# batteryCharger.net
KiCad netlist of a schematic drawn in EAGLE
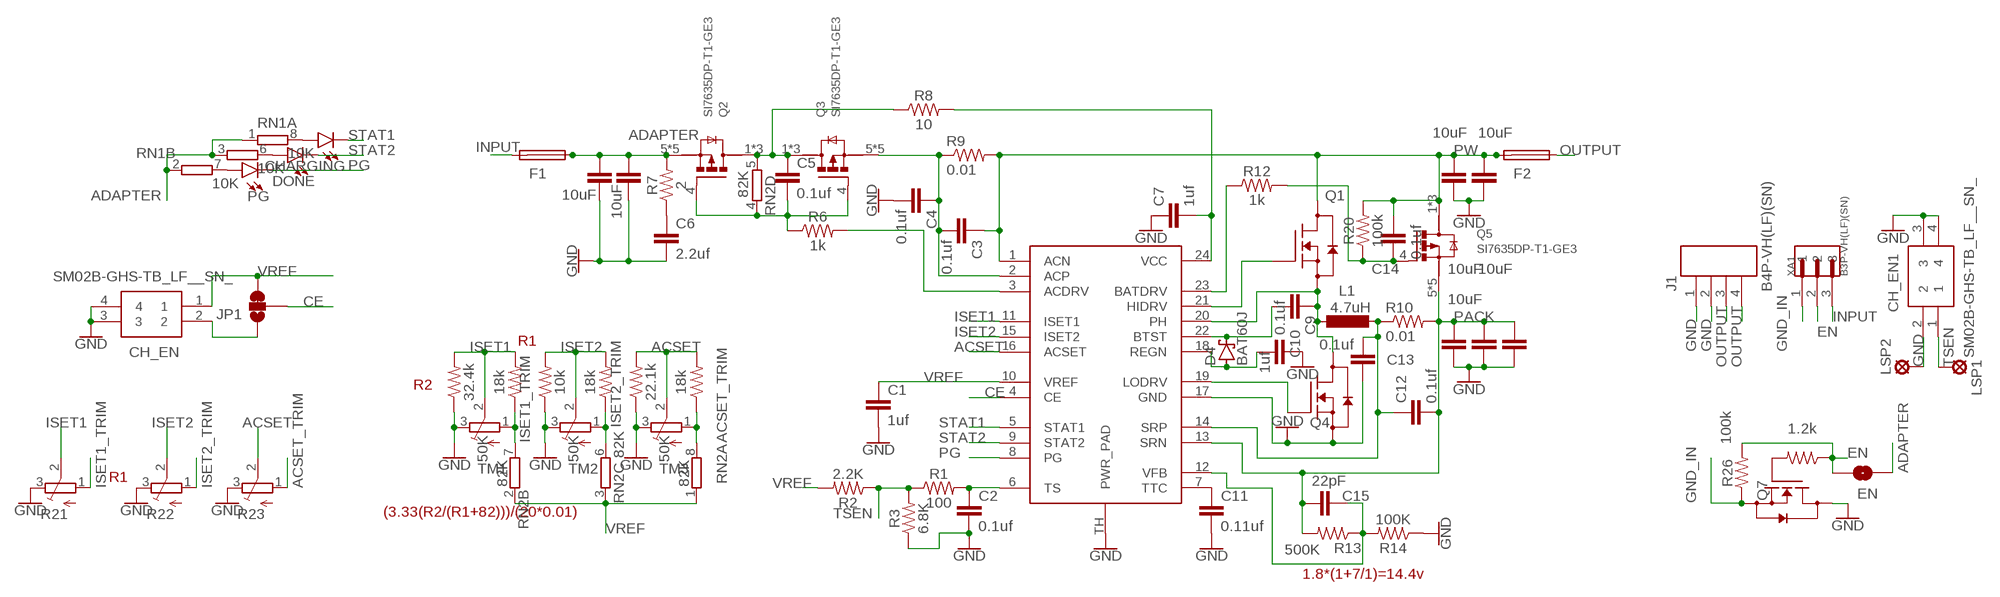
[diagram p0: schematic, sheet 1]

(export (version "E")
  (design (tool "Eeschema 10.0.6"))
  (components
    (comp (ref "C1")
      (value "1uf")
      (footprint "eagle-import:C0603")
      (libsource (lib "eagle-import") (part "C-EUC0603"))
    )
    (comp (ref "C2")
      (value "0.1uf")
      (footprint "eagle-import:C0603")
      (libsource (lib "eagle-import") (part "C-EUC0603"))
    )
    (comp (ref "C3")
      (value "0.1uf")
      (footprint "eagle-import:C0603")
      (libsource (lib "eagle-import") (part "C-EUC0603"))
    )
    (comp (ref "C4")
      (value "0.1uf")
      (footprint "eagle-import:C0603")
      (libsource (lib "eagle-import") (part "C-EUC0603"))
    )
    (comp (ref "C5")
      (value "0.1uf")
      (footprint "eagle-import:C0603")
      (libsource (lib "eagle-import") (part "C-EUC0603"))
    )
    (comp (ref "C6")
      (value "2.2uf")
      (footprint "eagle-import:C0603")
      (libsource (lib "eagle-import") (part "C-EUC0603"))
    )
    (comp (ref "C7")
      (value "1uf")
      (footprint "eagle-import:C0603")
      (libsource (lib "eagle-import") (part "C-EUC0603"))
    )
    (comp (ref "C9")
      (value "0.1uf")
      (footprint "eagle-import:C0603")
      (libsource (lib "eagle-import") (part "C-EUC0603"))
    )
    (comp (ref "C10")
      (value "1uf")
      (footprint "eagle-import:C0603")
      (libsource (lib "eagle-import") (part "C-EUC0603"))
    )
    (comp (ref "C11")
      (value "0.11uf")
      (footprint "eagle-import:C0603")
      (libsource (lib "eagle-import") (part "C-EUC0603"))
    )
    (comp (ref "C12")
      (value "0.1uf")
      (footprint "eagle-import:C0603")
      (libsource (lib "eagle-import") (part "C-EUC0603"))
    )
    (comp (ref "C13")
      (value "0.1uf")
      (footprint "eagle-import:C0603")
      (libsource (lib "eagle-import") (part "C-EUC0603"))
    )
    (comp (ref "C14")
      (value "0.1uf")
      (footprint "eagle-import:C0603")
      (libsource (lib "eagle-import") (part "C-EUC0603"))
    )
    (comp (ref "C15")
      (value "22pF")
      (footprint "eagle-import:C0603")
      (libsource (lib "eagle-import") (part "C-EUC0603"))
    )
    (comp (ref "C16")
      (value "10uF")
      (footprint "eagle-import:C1206")
      (libsource (lib "eagle-import") (part "C-EUC1206"))
    )
    (comp (ref "C17")
      (value "10uF")
      (footprint "eagle-import:C1206")
      (libsource (lib "eagle-import") (part "C-EUC1206"))
    )
    (comp (ref "C18")
      (value "10uF")
      (footprint "eagle-import:C1206")
      (libsource (lib "eagle-import") (part "C-EUC1206"))
    )
    (comp (ref "C19")
      (value "10uF")
      (footprint "eagle-import:C1206")
      (libsource (lib "eagle-import") (part "C-EUC1206"))
    )
    (comp (ref "C20")
      (value "10uF")
      (footprint "eagle-import:C1206")
      (libsource (lib "eagle-import") (part "C-EUC1206"))
    )
    (comp (ref "C21")
      (value "10uF")
      (footprint "eagle-import:C1206")
      (libsource (lib "eagle-import") (part "C-EUC1206"))
    )
    (comp (ref "C22")
      (value "10uF")
      (footprint "eagle-import:C1206")
      (libsource (lib "eagle-import") (part "C-EUC1206"))
    )
    (comp (ref "CHARGING")
      (value "LED1206")
      (footprint "eagle-import:LED-1206")
      (libsource (lib "eagle-import") (part "LED1206"))
    )
    (comp (ref "CH_EN")
      (value "SM02B-GHS-TB_LF__SN_")
      (footprint "eagle-import:SM02BGHSTBLFSN")
      (fields (field (name "ARROW_PART_NUMBER") "SM02B-GHS-TB(LF)(SN)"))
      (libsource (lib "eagle-import") (part "SM02B-GHS-TB_LF__SN_"))
    )
    (comp (ref "CH_EN1")
      (value "SM02B-GHS-TB_LF__SN_")
      (footprint "eagle-import:SM02BGHSTBLFSN")
      (fields (field (name "ARROW_PART_NUMBER") "SM02B-GHS-TB(LF)(SN)"))
      (libsource (lib "eagle-import") (part "SM02B-GHS-TB_LF__SN_"))
    )
    (comp (ref "D4")
      (value "BAT60J")
      (footprint "eagle-import:SOD323_ST")
      (libsource (lib "eagle-import") (part "BAT60J"))
    )
    (comp (ref "DONE")
      (value "LED1206")
      (footprint "eagle-import:LED-1206")
      (libsource (lib "eagle-import") (part "LED1206"))
    )
    (comp (ref "EN")
      (value "JUMPER-SMT_2_NO_SILK")
      (footprint "eagle-import:SMT-JUMPER_2_NO_SILK")
      (libsource (lib "eagle-import") (part "JUMPER-SMT_2_NO_SILK"))
    )
    (comp (ref "F1")
      (value "SMD-MICRO-FUSE-BLOCK")
      (footprint "eagle-import:OMNIBLOK")
      (libsource (lib "eagle-import") (part "SMD-MICRO-FUSE-BLOCK"))
    )
    (comp (ref "F2")
      (value "SMD-MICRO-FUSE-BLOCK")
      (footprint "eagle-import:OMNIBLOK")
      (libsource (lib "eagle-import") (part "SMD-MICRO-FUSE-BLOCK"))
    )
    (comp (ref "J1")
      (value "B4P-VH(LF)(SN)")
      (footprint "eagle-import:JST_B4P-VH(LF)(SN)")
      (fields (field (name "MF") "JST Sales"))
      (libsource (lib "eagle-import") (part "B4P-VH(LF)(SN)"))
    )
    (comp (ref "JP1")
      (value "JUMPER-SMT_3_1-NC_TRACE_NO-SILK")
      (footprint "eagle-import:SMT-JUMPER_3_1-NC_TRACE_NO-SILK")
      (libsource (lib "eagle-import") (part "JUMPER-SMT_3_1-NC_TRACE_NO-SILK"))
    )
    (comp (ref "L1")
      (value "4.7uH")
      (footprint "eagle-import:CEP125")
      (libsource (lib "eagle-import") (part "L-EUCEP125"))
    )
    (comp (ref "LSP1")
      (value "LSP10")
      (footprint "eagle-import:LSP10")
      (libsource (lib "eagle-import") (part "LSP10"))
    )
    (comp (ref "LSP2")
      (value "LSP10")
      (footprint "eagle-import:LSP10")
      (libsource (lib "eagle-import") (part "LSP10"))
    )
    (comp (ref "PG")
      (value "LED1206")
      (footprint "eagle-import:LED-1206")
      (libsource (lib "eagle-import") (part "LED1206"))
    )
    (comp (ref "Q1")
      (value "SIR414DP-T1-GE3")
      (footprint "eagle-import:TRANS_SQJ461EP-T1-GE3")
      (fields (field (name "MF") "Vishay Siliconix"))
      (libsource (lib "eagle-import") (part "SIR414DP-T1-GE3"))
    )
    (comp (ref "Q2")
      (value "SI7635DP-T1-GE3")
      (footprint "eagle-import:TRANS_SI7635DP-T1-GE3")
      (fields (field (name "MF") "Vishay"))
      (libsource (lib "eagle-import") (part "SI7635DP-T1-GE3"))
    )
    (comp (ref "Q3")
      (value "SI7635DP-T1-GE3")
      (footprint "eagle-import:TRANS_SI7635DP-T1-GE3")
      (fields (field (name "MF") "Vishay"))
      (libsource (lib "eagle-import") (part "SI7635DP-T1-GE3"))
    )
    (comp (ref "Q4")
      (value "SIR414DP-T1-GE3")
      (footprint "eagle-import:TRANS_SQJ461EP-T1-GE3")
      (fields (field (name "MF") "Vishay Siliconix"))
      (libsource (lib "eagle-import") (part "SIR414DP-T1-GE3"))
    )
    (comp (ref "Q5")
      (value "SI7635DP-T1-GE3")
      (footprint "eagle-import:TRANS_SI7635DP-T1-GE3")
      (fields (field (name "MF") "Vishay"))
      (libsource (lib "eagle-import") (part "SI7635DP-T1-GE3"))
    )
    (comp (ref "Q7")
      (value "SIR414DP-T1-GE3")
      (footprint "eagle-import:TRANS_SQJ461EP-T1-GE3")
      (fields (field (name "MF") "Vishay Siliconix"))
      (libsource (lib "eagle-import") (part "SIR414DP-T1-GE3"))
    )
    (comp (ref "R1")
      (value "100")
      (footprint "eagle-import:0603")
      (libsource (lib "eagle-import") (part "RESISTOR0603"))
    )
    (comp (ref "R2")
      (value "2.2K")
      (footprint "eagle-import:0603")
      (libsource (lib "eagle-import") (part "RESISTOR0603"))
    )
    (comp (ref "R3")
      (value "6.8K")
      (footprint "eagle-import:0603")
      (libsource (lib "eagle-import") (part "RESISTOR0603"))
    )
    (comp (ref "R4")
      (value "32.4k")
      (footprint "eagle-import:0603")
      (libsource (lib "eagle-import") (part "RESISTOR0603"))
    )
    (comp (ref "R5")
      (value "18k")
      (footprint "eagle-import:0603")
      (libsource (lib "eagle-import") (part "RESISTOR0603"))
    )
    (comp (ref "R6")
      (value "1k")
      (footprint "eagle-import:0603")
      (libsource (lib "eagle-import") (part "RESISTOR0603"))
    )
    (comp (ref "R7")
      (value "2")
      (footprint "eagle-import:0603")
      (libsource (lib "eagle-import") (part "RESISTOR0603"))
    )
    (comp (ref "R8")
      (value "10")
      (footprint "eagle-import:0603")
      (libsource (lib "eagle-import") (part "RESISTOR0603"))
    )
    (comp (ref "R9")
      (value "0.01")
      (footprint "eagle-import:R1206")
      (libsource (lib "eagle-import") (part "R-US_R1206"))
    )
    (comp (ref "R10")
      (value "0.01")
      (footprint "eagle-import:R1206")
      (libsource (lib "eagle-import") (part "R-US_R1206"))
    )
    (comp (ref "R12")
      (value "1k")
      (footprint "eagle-import:0603")
      (libsource (lib "eagle-import") (part "RESISTOR0603"))
    )
    (comp (ref "R13")
      (value "500K")
      (footprint "eagle-import:0603")
      (libsource (lib "eagle-import") (part "RESISTOR0603"))
    )
    (comp (ref "R14")
      (value "100K")
      (footprint "eagle-import:0603")
      (libsource (lib "eagle-import") (part "RESISTOR0603"))
    )
    (comp (ref "R16")
      (value "10k")
      (footprint "eagle-import:0603")
      (libsource (lib "eagle-import") (part "RESISTOR0603"))
    )
    (comp (ref "R17")
      (value "18k")
      (footprint "eagle-import:0603")
      (libsource (lib "eagle-import") (part "RESISTOR0603"))
    )
    (comp (ref "R18")
      (value "22.1k")
      (footprint "eagle-import:0603")
      (libsource (lib "eagle-import") (part "RESISTOR0603"))
    )
    (comp (ref "R19")
      (value "18k")
      (footprint "eagle-import:0603")
      (libsource (lib "eagle-import") (part "RESISTOR0603"))
    )
    (comp (ref "R20")
      (value "100k")
      (footprint "eagle-import:0603")
      (libsource (lib "eagle-import") (part "RESISTOR0603"))
    )
    (comp (ref "R21")
      (value "TRIM_EU-3223W")
      (footprint "eagle-import:3223W")
      (libsource (lib "eagle-import") (part "TRIM_EU-3223W"))
    )
    (comp (ref "R22")
      (value "TRIM_EU-3223W")
      (footprint "eagle-import:3223W")
      (libsource (lib "eagle-import") (part "TRIM_EU-3223W"))
    )
    (comp (ref "R23")
      (value "TRIM_EU-3223W")
      (footprint "eagle-import:3223W")
      (libsource (lib "eagle-import") (part "TRIM_EU-3223W"))
    )
    (comp (ref "R25")
      (value "1.2k")
      (footprint "eagle-import:0603")
      (libsource (lib "eagle-import") (part "RESISTOR0603"))
    )
    (comp (ref "R26")
      (value "100k")
      (footprint "eagle-import:0603")
      (libsource (lib "eagle-import") (part "RESISTOR0603"))
    )
    (comp (ref "RN1")
      (value "10K")
      (footprint "eagle-import:0603-ARC")
      (libsource (lib "eagle-import") (part "4R-N0603-ARC"))
    )
    (comp (ref "RN2")
      (value "82K")
      (footprint "eagle-import:CAY16")
      (libsource (lib "eagle-import") (part "4R-NCAY16"))
    )
    (comp (ref "TM1")
      (value "50K")
      (footprint "eagle-import:TC33X")
      (libsource (lib "eagle-import") (part "TRIMPOTTC33X"))
    )
    (comp (ref "TM2")
      (value "50K")
      (footprint "eagle-import:TC33X")
      (libsource (lib "eagle-import") (part "TRIMPOTTC33X"))
    )
    (comp (ref "TM3")
      (value "50K")
      (footprint "eagle-import:TC33X")
      (libsource (lib "eagle-import") (part "TRIMPOTTC33X"))
    )
    (comp (ref "U$1")
      (value "BQ24630VQFN24")
      (footprint "eagle-import:HVQFN24")
      (libsource (lib "eagle-import") (part "BQ24630VQFN24"))
    )
    (comp (ref "XA1")
      (value "B3P-VH(LF)(SN)")
      (footprint "eagle-import:JST_B3P-VH(LF)(SN)")
      (fields (field (name "MF") "JST Sales"))
      (libsource (lib "eagle-import") (part "B3P-VH(LF)(SN)"))
    )
  )
  (nets
    (net (code "1") (name "/ACSET") (class "Default")
      (node (ref "R18") (pin "2") (pinfunction "2_2") (pintype "passive"))
      (node (ref "R19") (pin "2") (pinfunction "2_2") (pintype "passive"))
      (node (ref "R23") (pin "2") (pinfunction "S_2") (pintype "passive"))
      (node (ref "TM3") (pin "2") (pinfunction "S_2") (pintype "passive"))
      (node (ref "U$1") (pin "16") (pinfunction "ACSET_16") (pintype "bidirectional"))
    )
    (net (code "2") (name "/ACSET_TRIM") (class "Default")
      (node (ref "R19") (pin "1") (pinfunction "1_1") (pintype "passive"))
      (node (ref "R23") (pin "1") (pinfunction "A_1") (pintype "passive"))
      (node (ref "RN2") (pin "8") (pinfunction "2_8") (pintype "passive"))
      (node (ref "TM3") (pin "1") (pinfunction "A_1") (pintype "passive"))
    )
    (net (code "3") (name "/ADAPTER") (class "Default")
      (node (ref "C21") (pin "1") (pinfunction "1_1") (pintype "passive"))
      (node (ref "C22") (pin "1") (pinfunction "1_1") (pintype "passive"))
      (node (ref "EN") (pin "1") (pinfunction "1_1") (pintype "passive"))
      (node (ref "F1") (pin "P$1") (pinfunction "1_P$1") (pintype "passive"))
      (node (ref "Q2") (pin "5") (pinfunction "D_5") (pintype "passive"))
      (node (ref "Q2") (pin "6") (pinfunction "D_6") (pintype "passive"))
      (node (ref "Q2") (pin "7") (pinfunction "D_7") (pintype "passive"))
      (node (ref "Q2") (pin "8") (pinfunction "D_8") (pintype "passive"))
      (node (ref "Q2") (pin "9") (pinfunction "D_9") (pintype "passive"))
      (node (ref "R7") (pin "2") (pinfunction "2_2") (pintype "passive"))
      (node (ref "RN1") (pin "1") (pinfunction "1_1") (pintype "passive"))
      (node (ref "RN1") (pin "2") (pinfunction "1_2") (pintype "passive"))
      (node (ref "RN1") (pin "3") (pinfunction "1_3") (pintype "passive"))
    )
    (net (code "4") (name "/CE") (class "Default")
      (node (ref "JP1") (pin "2") (pinfunction "2_2") (pintype "passive"))
      (node (ref "U$1") (pin "4") (pinfunction "CE_4") (pintype "bidirectional"))
    )
    (net (code "5") (name "/EN") (class "Default")
      (node (ref "EN") (pin "2") (pinfunction "2_2") (pintype "passive"))
      (node (ref "R25") (pin "1") (pinfunction "1_1") (pintype "passive"))
      (node (ref "R26") (pin "2") (pinfunction "2_2") (pintype "passive"))
      (node (ref "XA1") (pin "2") (pinfunction "2_2") (pintype "passive"))
    )
    (net (code "6") (name "/GND_IN") (class "Default")
      (node (ref "Q7") (pin "1") (pinfunction "S_1") (pintype "passive"))
      (node (ref "Q7") (pin "2") (pinfunction "S_2") (pintype "passive"))
      (node (ref "Q7") (pin "3") (pinfunction "S_3") (pintype "passive"))
      (node (ref "R26") (pin "1") (pinfunction "1_1") (pintype "passive"))
      (node (ref "XA1") (pin "1") (pinfunction "1_1") (pintype "passive"))
    )
    (net (code "7") (name "/INPUT") (class "Default")
      (node (ref "F1") (pin "P$2") (pinfunction "2_P$2") (pintype "passive"))
      (node (ref "XA1") (pin "3") (pinfunction "3_3") (pintype "passive"))
    )
    (net (code "8") (name "/ISET1") (class "Default")
      (node (ref "R21") (pin "2") (pinfunction "S_2") (pintype "passive"))
      (node (ref "R4") (pin "2") (pinfunction "2_2") (pintype "passive"))
      (node (ref "R5") (pin "2") (pinfunction "2_2") (pintype "passive"))
      (node (ref "TM1") (pin "2") (pinfunction "S_2") (pintype "passive"))
      (node (ref "U$1") (pin "11") (pinfunction "ISET1_11") (pintype "bidirectional"))
    )
    (net (code "9") (name "/ISET1_TRIM") (class "Default")
      (node (ref "R21") (pin "1") (pinfunction "A_1") (pintype "passive"))
      (node (ref "R5") (pin "1") (pinfunction "1_1") (pintype "passive"))
      (node (ref "RN2") (pin "7") (pinfunction "2_7") (pintype "passive"))
      (node (ref "TM1") (pin "1") (pinfunction "A_1") (pintype "passive"))
    )
    (net (code "10") (name "/ISET2") (class "Default")
      (node (ref "R16") (pin "2") (pinfunction "2_2") (pintype "passive"))
      (node (ref "R17") (pin "2") (pinfunction "2_2") (pintype "passive"))
      (node (ref "R22") (pin "2") (pinfunction "S_2") (pintype "passive"))
      (node (ref "TM2") (pin "2") (pinfunction "S_2") (pintype "passive"))
      (node (ref "U$1") (pin "15") (pinfunction "ISET2_15") (pintype "bidirectional"))
    )
    (net (code "11") (name "/ISET2_TRIM") (class "Default")
      (node (ref "R17") (pin "1") (pinfunction "1_1") (pintype "passive"))
      (node (ref "R22") (pin "1") (pinfunction "A_1") (pintype "passive"))
      (node (ref "RN2") (pin "6") (pinfunction "2_6") (pintype "passive"))
      (node (ref "TM2") (pin "1") (pinfunction "A_1") (pintype "passive"))
    )
    (net (code "12") (name "/OUTPUT") (class "Default")
      (node (ref "F2") (pin "P$1") (pinfunction "1_P$1") (pintype "passive"))
      (node (ref "J1") (pin "3") (pinfunction "3_3") (pintype "passive"))
      (node (ref "J1") (pin "4") (pinfunction "4_4") (pintype "passive"))
    )
    (net (code "13") (name "/PACK") (class "Default")
      (node (ref "C12") (pin "2") (pinfunction "2_2") (pintype "passive"))
      (node (ref "C15") (pin "2") (pinfunction "2_2") (pintype "passive"))
      (node (ref "C16") (pin "1") (pinfunction "1_1") (pintype "passive"))
      (node (ref "C17") (pin "1") (pinfunction "1_1") (pintype "passive"))
      (node (ref "C18") (pin "1") (pinfunction "1_1") (pintype "passive"))
      (node (ref "Q5") (pin "5") (pinfunction "D_5") (pintype "passive"))
      (node (ref "Q5") (pin "6") (pinfunction "D_6") (pintype "passive"))
      (node (ref "Q5") (pin "7") (pinfunction "D_7") (pintype "passive"))
      (node (ref "Q5") (pin "8") (pinfunction "D_8") (pintype "passive"))
      (node (ref "Q5") (pin "9") (pinfunction "D_9") (pintype "passive"))
      (node (ref "R10") (pin "2") (pinfunction "2_2") (pintype "passive"))
      (node (ref "R13") (pin "2") (pinfunction "2_2") (pintype "passive"))
      (node (ref "U$1") (pin "13") (pinfunction "SRN_13") (pintype "bidirectional"))
    )
    (net (code "14") (name "/PG") (class "Default")
      (node (ref "PG") (pin "C") (pinfunction "C_C") (pintype "passive"))
      (node (ref "U$1") (pin "8") (pinfunction "PG_8") (pintype "bidirectional"))
    )
    (net (code "15") (name "/PW") (class "Default")
      (node (ref "C14") (pin "2") (pinfunction "2_2") (pintype "passive"))
      (node (ref "C19") (pin "1") (pinfunction "1_1") (pintype "passive"))
      (node (ref "C20") (pin "1") (pinfunction "1_1") (pintype "passive"))
      (node (ref "C3") (pin "1") (pinfunction "1_1") (pintype "passive"))
      (node (ref "F2") (pin "P$2") (pinfunction "2_P$2") (pintype "passive"))
      (node (ref "Q1") (pin "5") (pinfunction "D_5") (pintype "passive"))
      (node (ref "Q1") (pin "6") (pinfunction "D_6") (pintype "passive"))
      (node (ref "Q1") (pin "7") (pinfunction "D_7") (pintype "passive"))
      (node (ref "Q1") (pin "8") (pinfunction "D_8") (pintype "passive"))
      (node (ref "Q1") (pin "9") (pinfunction "D_9") (pintype "passive"))
      (node (ref "Q5") (pin "1") (pinfunction "S_1") (pintype "passive"))
      (node (ref "Q5") (pin "2") (pinfunction "S_2") (pintype "passive"))
      (node (ref "Q5") (pin "3") (pinfunction "S_3") (pintype "passive"))
      (node (ref "R20") (pin "2") (pinfunction "2_2") (pintype "passive"))
      (node (ref "R9") (pin "2") (pinfunction "2_2") (pintype "passive"))
      (node (ref "U$1") (pin "1") (pinfunction "ACN_1") (pintype "bidirectional"))
    )
    (net (code "16") (name "/STAT1") (class "Default")
      (node (ref "CHARGING") (pin "C") (pinfunction "C_C") (pintype "passive"))
      (node (ref "U$1") (pin "5") (pinfunction "STAT1_5") (pintype "bidirectional"))
    )
    (net (code "17") (name "/STAT2") (class "Default")
      (node (ref "DONE") (pin "C") (pinfunction "C_C") (pintype "passive"))
      (node (ref "U$1") (pin "9") (pinfunction "STAT2_9") (pintype "bidirectional"))
    )
    (net (code "18") (name "/TSEN") (class "Default")
      (node (ref "CH_EN1") (pin "1") (pinfunction "1_1") (pintype "bidirectional"))
      (node (ref "LSP1") (pin "MP") (pinfunction "MP_MP") (pintype "passive"))
      (node (ref "R1") (pin "1") (pinfunction "1_1") (pintype "passive"))
      (node (ref "R2") (pin "1") (pinfunction "1_1") (pintype "passive"))
      (node (ref "R3") (pin "2") (pinfunction "2_2") (pintype "passive"))
    )
    (net (code "19") (name "/VREF") (class "Default")
      (node (ref "C1") (pin "1") (pinfunction "1_1") (pintype "passive"))
      (node (ref "CH_EN") (pin "1") (pinfunction "1_1") (pintype "bidirectional"))
      (node (ref "JP1") (pin "3") (pinfunction "3_3") (pintype "passive"))
      (node (ref "R2") (pin "2") (pinfunction "2_2") (pintype "passive"))
      (node (ref "RN2") (pin "1") (pinfunction "1_1") (pintype "passive"))
      (node (ref "RN2") (pin "2") (pinfunction "1_2") (pintype "passive"))
      (node (ref "RN2") (pin "3") (pinfunction "1_3") (pintype "passive"))
      (node (ref "U$1") (pin "10") (pinfunction "VREF_10") (pintype "bidirectional"))
    )
    (net (code "20") (name "GND") (class "Default")
      (node (ref "C1") (pin "2") (pinfunction "2_2") (pintype "passive"))
      (node (ref "C10") (pin "2") (pinfunction "2_2") (pintype "passive"))
      (node (ref "C11") (pin "2") (pinfunction "2_2") (pintype "passive"))
      (node (ref "C13") (pin "1") (pinfunction "1_1") (pintype "passive"))
      (node (ref "C16") (pin "2") (pinfunction "2_2") (pintype "passive"))
      (node (ref "C17") (pin "2") (pinfunction "2_2") (pintype "passive"))
      (node (ref "C18") (pin "2") (pinfunction "2_2") (pintype "passive"))
      (node (ref "C19") (pin "2") (pinfunction "2_2") (pintype "passive"))
      (node (ref "C2") (pin "2") (pinfunction "2_2") (pintype "passive"))
      (node (ref "C20") (pin "2") (pinfunction "2_2") (pintype "passive"))
      (node (ref "C21") (pin "2") (pinfunction "2_2") (pintype "passive"))
      (node (ref "C22") (pin "2") (pinfunction "2_2") (pintype "passive"))
      (node (ref "C4") (pin "2") (pinfunction "2_2") (pintype "passive"))
      (node (ref "C6") (pin "2") (pinfunction "2_2") (pintype "passive"))
      (node (ref "C7") (pin "1") (pinfunction "1_1") (pintype "passive"))
      (node (ref "CH_EN") (pin "3") (pinfunction "3_3") (pintype "bidirectional"))
      (node (ref "CH_EN") (pin "4") (pinfunction "4_4") (pintype "bidirectional"))
      (node (ref "CH_EN1") (pin "2") (pinfunction "2_2") (pintype "bidirectional"))
      (node (ref "CH_EN1") (pin "3") (pinfunction "3_3") (pintype "bidirectional"))
      (node (ref "CH_EN1") (pin "4") (pinfunction "4_4") (pintype "bidirectional"))
      (node (ref "J1") (pin "1") (pinfunction "1_1") (pintype "passive"))
      (node (ref "J1") (pin "2") (pinfunction "2_2") (pintype "passive"))
      (node (ref "LSP2") (pin "MP") (pinfunction "MP_MP") (pintype "passive"))
      (node (ref "Q4") (pin "1") (pinfunction "S_1") (pintype "passive"))
      (node (ref "Q4") (pin "2") (pinfunction "S_2") (pintype "passive"))
      (node (ref "Q4") (pin "3") (pinfunction "S_3") (pintype "passive"))
      (node (ref "Q7") (pin "5") (pinfunction "D_5") (pintype "passive"))
      (node (ref "Q7") (pin "6") (pinfunction "D_6") (pintype "passive"))
      (node (ref "Q7") (pin "7") (pinfunction "D_7") (pintype "passive"))
      (node (ref "Q7") (pin "8") (pinfunction "D_8") (pintype "passive"))
      (node (ref "Q7") (pin "9") (pinfunction "D_9") (pintype "passive"))
      (node (ref "R14") (pin "1") (pinfunction "1_1") (pintype "passive"))
      (node (ref "R16") (pin "1") (pinfunction "1_1") (pintype "passive"))
      (node (ref "R18") (pin "1") (pinfunction "1_1") (pintype "passive"))
      (node (ref "R21") (pin "3") (pinfunction "E_3") (pintype "passive"))
      (node (ref "R22") (pin "3") (pinfunction "E_3") (pintype "passive"))
      (node (ref "R23") (pin "3") (pinfunction "E_3") (pintype "passive"))
      (node (ref "R3") (pin "1") (pinfunction "1_1") (pintype "passive"))
      (node (ref "R4") (pin "1") (pinfunction "1_1") (pintype "passive"))
      (node (ref "TM1") (pin "3") (pinfunction "E_3") (pintype "passive"))
      (node (ref "TM2") (pin "3") (pinfunction "E_3") (pintype "passive"))
      (node (ref "TM3") (pin "3") (pinfunction "E_3") (pintype "passive"))
      (node (ref "U$1") (pin "17") (pinfunction "GND_17") (pintype "bidirectional"))
      (node (ref "U$1") (pin "TH") (pinfunction "PWR_PAD_TH") (pintype "bidirectional"))
    )
    (net (code "21") (name "Net-(C6-Pad1)") (class "Default")
      (node (ref "C6") (pin "1") (pinfunction "1_1") (pintype "passive"))
      (node (ref "R7") (pin "1") (pinfunction "1_1") (pintype "passive"))
    )
    (net (code "22") (name "Net-(CH_EN-Pad2)") (class "Default")
      (node (ref "CH_EN") (pin "2") (pinfunction "2_2") (pintype "bidirectional"))
      (node (ref "JP1") (pin "1") (pinfunction "1_1") (pintype "passive"))
    )
    (net (code "23") (name "Net-(Q1-G)") (class "Default")
      (node (ref "Q1") (pin "4") (pinfunction "G_4") (pintype "passive"))
      (node (ref "U$1") (pin "21") (pinfunction "HIDRV_21") (pintype "bidirectional"))
    )
    (net (code "24") (name "Net-(Q2-G)") (class "Default")
      (node (ref "C5") (pin "2") (pinfunction "2_2") (pintype "passive"))
      (node (ref "Q2") (pin "4") (pinfunction "G_4") (pintype "passive"))
      (node (ref "Q3") (pin "4") (pinfunction "G_4") (pintype "passive"))
      (node (ref "R6") (pin "1") (pinfunction "1_1") (pintype "passive"))
      (node (ref "RN2") (pin "4") (pinfunction "1_4") (pintype "passive"))
    )
    (net (code "25") (name "Net-(Q4-G)") (class "Default")
      (node (ref "Q4") (pin "4") (pinfunction "G_4") (pintype "passive"))
      (node (ref "U$1") (pin "19") (pinfunction "LODRV_19") (pintype "bidirectional"))
    )
    (net (code "26") (name "Net-(Q5-G)") (class "Default")
      (node (ref "C14") (pin "1") (pinfunction "1_1") (pintype "passive"))
      (node (ref "Q5") (pin "4") (pinfunction "G_4") (pintype "passive"))
      (node (ref "R12") (pin "2") (pinfunction "2_2") (pintype "passive"))
      (node (ref "R20") (pin "1") (pinfunction "1_1") (pintype "passive"))
    )
    (net (code "27") (name "Net-(Q7-G)") (class "Default")
      (node (ref "Q7") (pin "4") (pinfunction "G_4") (pintype "passive"))
      (node (ref "R25") (pin "2") (pinfunction "2_2") (pintype "passive"))
    )
    (net (code "28") (name "Net-(RN1A-2)") (class "Default")
      (node (ref "CHARGING") (pin "A") (pinfunction "A_A") (pintype "passive"))
      (node (ref "RN1") (pin "8") (pinfunction "2_8") (pintype "passive"))
    )
    (net (code "29") (name "Net-(RN1B-2)") (class "Default")
      (node (ref "PG") (pin "A") (pinfunction "A_A") (pintype "passive"))
      (node (ref "RN1") (pin "7") (pinfunction "2_7") (pintype "passive"))
    )
    (net (code "30") (name "Net-(RN1C-2)") (class "Default")
      (node (ref "DONE") (pin "A") (pinfunction "A_A") (pintype "passive"))
      (node (ref "RN1") (pin "6") (pinfunction "2_6") (pintype "passive"))
    )
    (net (code "31") (name "Net-(RN2D-2)") (class "Default")
      (node (ref "C5") (pin "1") (pinfunction "1_1") (pintype "passive"))
      (node (ref "Q2") (pin "1") (pinfunction "S_1") (pintype "passive"))
      (node (ref "Q2") (pin "2") (pinfunction "S_2") (pintype "passive"))
      (node (ref "Q2") (pin "3") (pinfunction "S_3") (pintype "passive"))
      (node (ref "Q3") (pin "1") (pinfunction "S_1") (pintype "passive"))
      (node (ref "Q3") (pin "2") (pinfunction "S_2") (pintype "passive"))
      (node (ref "Q3") (pin "3") (pinfunction "S_3") (pintype "passive"))
      (node (ref "R8") (pin "1") (pinfunction "1_1") (pintype "passive"))
      (node (ref "RN2") (pin "5") (pinfunction "2_5") (pintype "passive"))
    )
    (net (code "32") (name "Net-(U$1-ACDRV)") (class "Default")
      (node (ref "R6") (pin "2") (pinfunction "2_2") (pintype "passive"))
      (node (ref "U$1") (pin "3") (pinfunction "ACDRV_3") (pintype "bidirectional"))
    )
    (net (code "33") (name "Net-(U$1-ACP)") (class "Default")
      (node (ref "C3") (pin "2") (pinfunction "2_2") (pintype "passive"))
      (node (ref "C4") (pin "1") (pinfunction "1_1") (pintype "passive"))
      (node (ref "Q3") (pin "5") (pinfunction "D_5") (pintype "passive"))
      (node (ref "Q3") (pin "6") (pinfunction "D_6") (pintype "passive"))
      (node (ref "Q3") (pin "7") (pinfunction "D_7") (pintype "passive"))
      (node (ref "Q3") (pin "8") (pinfunction "D_8") (pintype "passive"))
      (node (ref "Q3") (pin "9") (pinfunction "D_9") (pintype "passive"))
      (node (ref "R9") (pin "1") (pinfunction "1_1") (pintype "passive"))
      (node (ref "U$1") (pin "2") (pinfunction "ACP_2") (pintype "bidirectional"))
    )
    (net (code "34") (name "Net-(U$1-BATDRV)") (class "Default")
      (node (ref "R12") (pin "1") (pinfunction "1_1") (pintype "passive"))
      (node (ref "U$1") (pin "23") (pinfunction "BATDRV_23") (pintype "bidirectional"))
    )
    (net (code "35") (name "Net-(U$1-BTST)") (class "Default")
      (node (ref "C9") (pin "2") (pinfunction "2_2") (pintype "passive"))
      (node (ref "D4") (pin "C") (pinfunction "C_C") (pintype "passive"))
      (node (ref "U$1") (pin "22") (pinfunction "BTST_22") (pintype "bidirectional"))
    )
    (net (code "36") (name "Net-(U$1-PH)") (class "Default")
      (node (ref "C9") (pin "1") (pinfunction "1_1") (pintype "passive"))
      (node (ref "L1") (pin "1") (pinfunction "1_1") (pintype "passive"))
      (node (ref "Q1") (pin "1") (pinfunction "S_1") (pintype "passive"))
      (node (ref "Q1") (pin "2") (pinfunction "S_2") (pintype "passive"))
      (node (ref "Q1") (pin "3") (pinfunction "S_3") (pintype "passive"))
      (node (ref "Q4") (pin "5") (pinfunction "D_5") (pintype "passive"))
      (node (ref "Q4") (pin "6") (pinfunction "D_6") (pintype "passive"))
      (node (ref "Q4") (pin "7") (pinfunction "D_7") (pintype "passive"))
      (node (ref "Q4") (pin "8") (pinfunction "D_8") (pintype "passive"))
      (node (ref "Q4") (pin "9") (pinfunction "D_9") (pintype "passive"))
      (node (ref "U$1") (pin "20") (pinfunction "PH_20") (pintype "bidirectional"))
    )
    (net (code "37") (name "Net-(U$1-REGN)") (class "Default")
      (node (ref "C10") (pin "1") (pinfunction "1_1") (pintype "passive"))
      (node (ref "D4") (pin "A") (pinfunction "A_A") (pintype "passive"))
      (node (ref "U$1") (pin "18") (pinfunction "REGN_18") (pintype "bidirectional"))
    )
    (net (code "38") (name "Net-(U$1-SRP)") (class "Default")
      (node (ref "C12") (pin "1") (pinfunction "1_1") (pintype "passive"))
      (node (ref "C13") (pin "2") (pinfunction "2_2") (pintype "passive"))
      (node (ref "L1") (pin "2") (pinfunction "2_2") (pintype "passive"))
      (node (ref "R10") (pin "1") (pinfunction "1_1") (pintype "passive"))
      (node (ref "U$1") (pin "14") (pinfunction "SRP_14") (pintype "bidirectional"))
    )
    (net (code "39") (name "Net-(U$1-TS)") (class "Default")
      (node (ref "C2") (pin "1") (pinfunction "1_1") (pintype "passive"))
      (node (ref "R1") (pin "2") (pinfunction "2_2") (pintype "passive"))
      (node (ref "U$1") (pin "6") (pinfunction "TS_6") (pintype "bidirectional"))
    )
    (net (code "40") (name "Net-(U$1-TTC)") (class "Default")
      (node (ref "C11") (pin "1") (pinfunction "1_1") (pintype "passive"))
      (node (ref "U$1") (pin "7") (pinfunction "TTC_7") (pintype "bidirectional"))
    )
    (net (code "41") (name "Net-(U$1-VCC)") (class "Default")
      (node (ref "C7") (pin "2") (pinfunction "2_2") (pintype "passive"))
      (node (ref "R8") (pin "2") (pinfunction "2_2") (pintype "passive"))
      (node (ref "U$1") (pin "24") (pinfunction "VCC_24") (pintype "bidirectional"))
    )
    (net (code "42") (name "Net-(U$1-VFB)") (class "Default")
      (node (ref "C15") (pin "1") (pinfunction "1_1") (pintype "passive"))
      (node (ref "R13") (pin "1") (pinfunction "1_1") (pintype "passive"))
      (node (ref "R14") (pin "2") (pinfunction "2_2") (pintype "passive"))
      (node (ref "U$1") (pin "12") (pinfunction "VFB_12") (pintype "bidirectional"))
    )
  )
)
